# valve.net
KiCad netlist of a schematic drawn in EAGLE
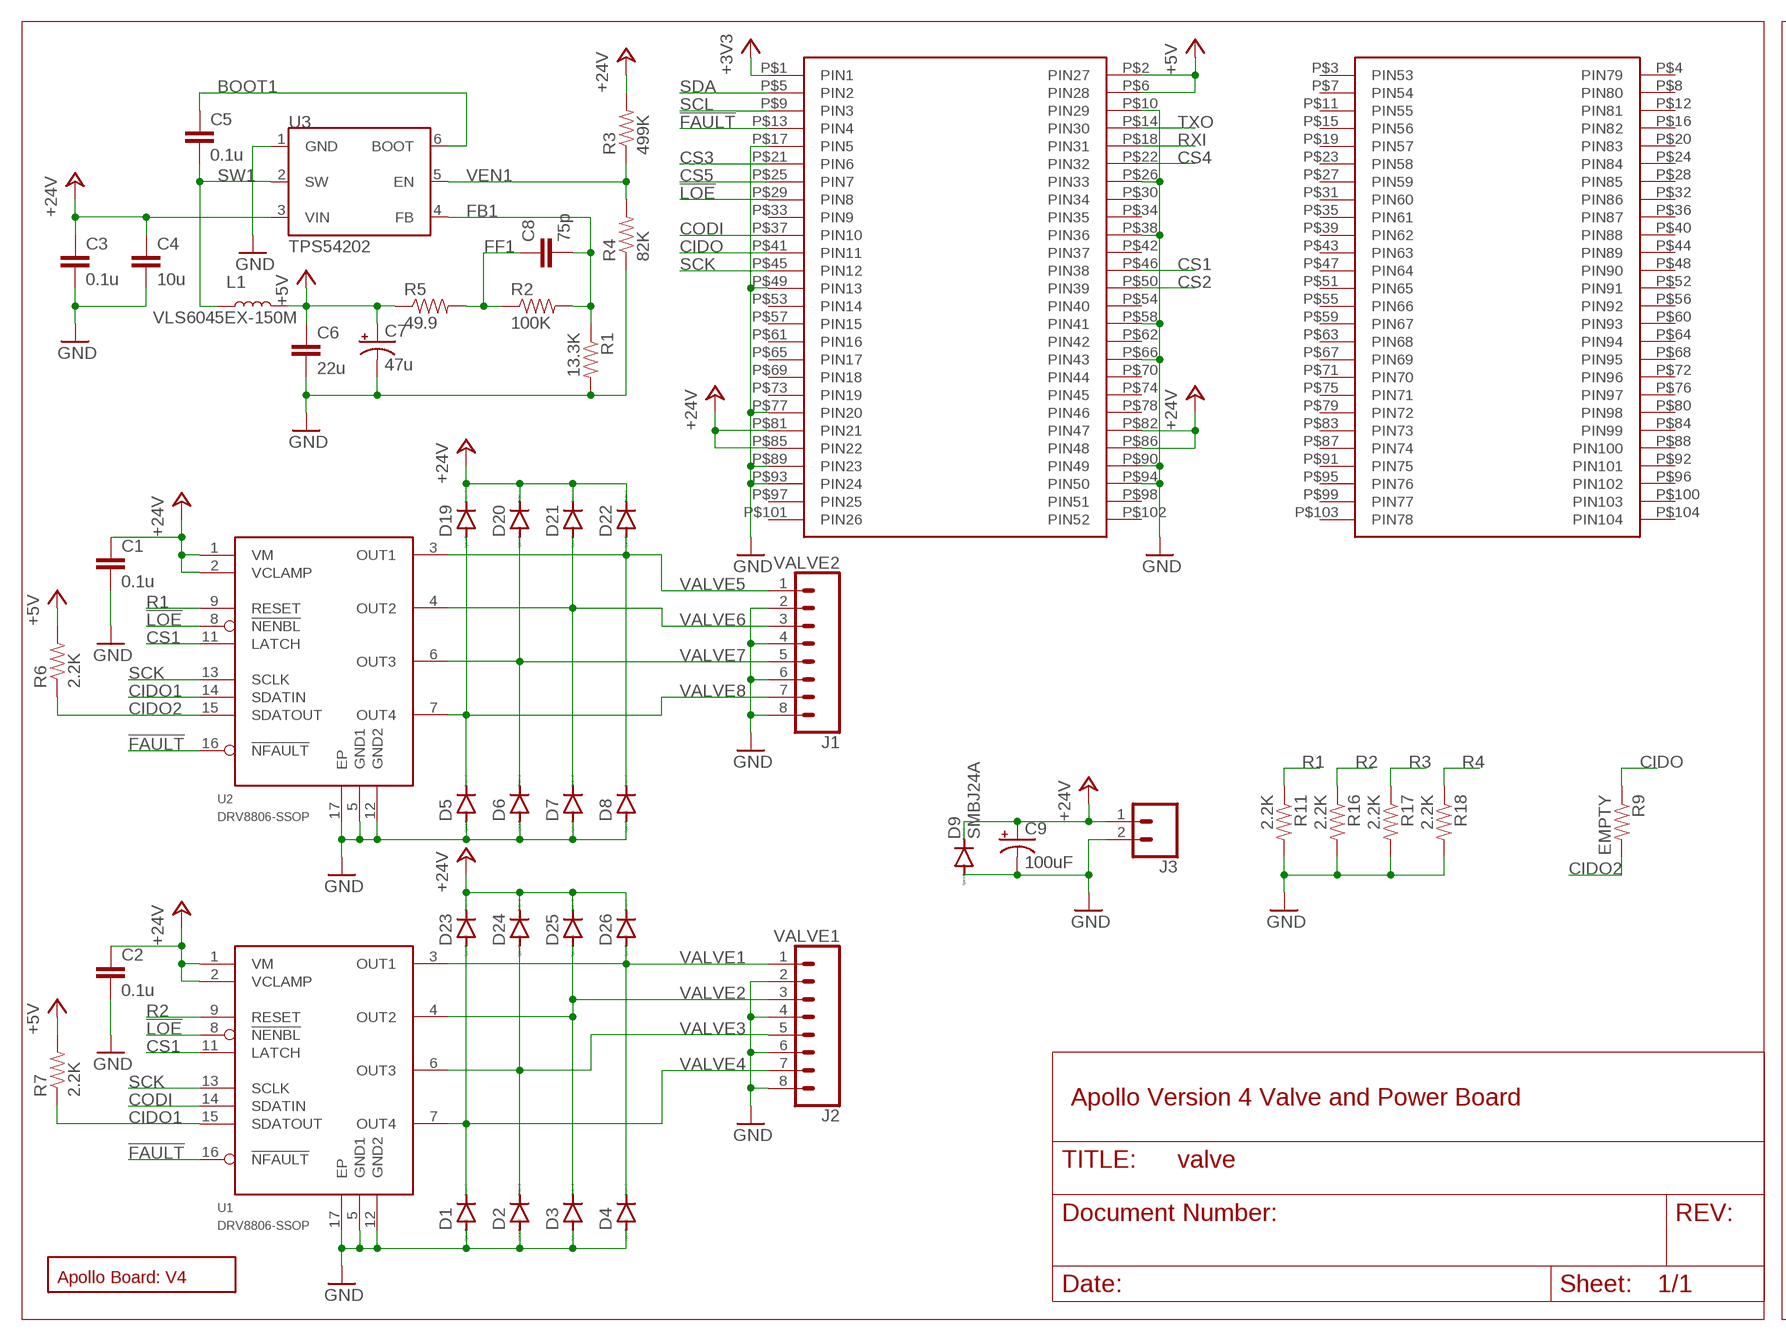
[diagram p0: schematic, sheet 1, part 1 of 2]
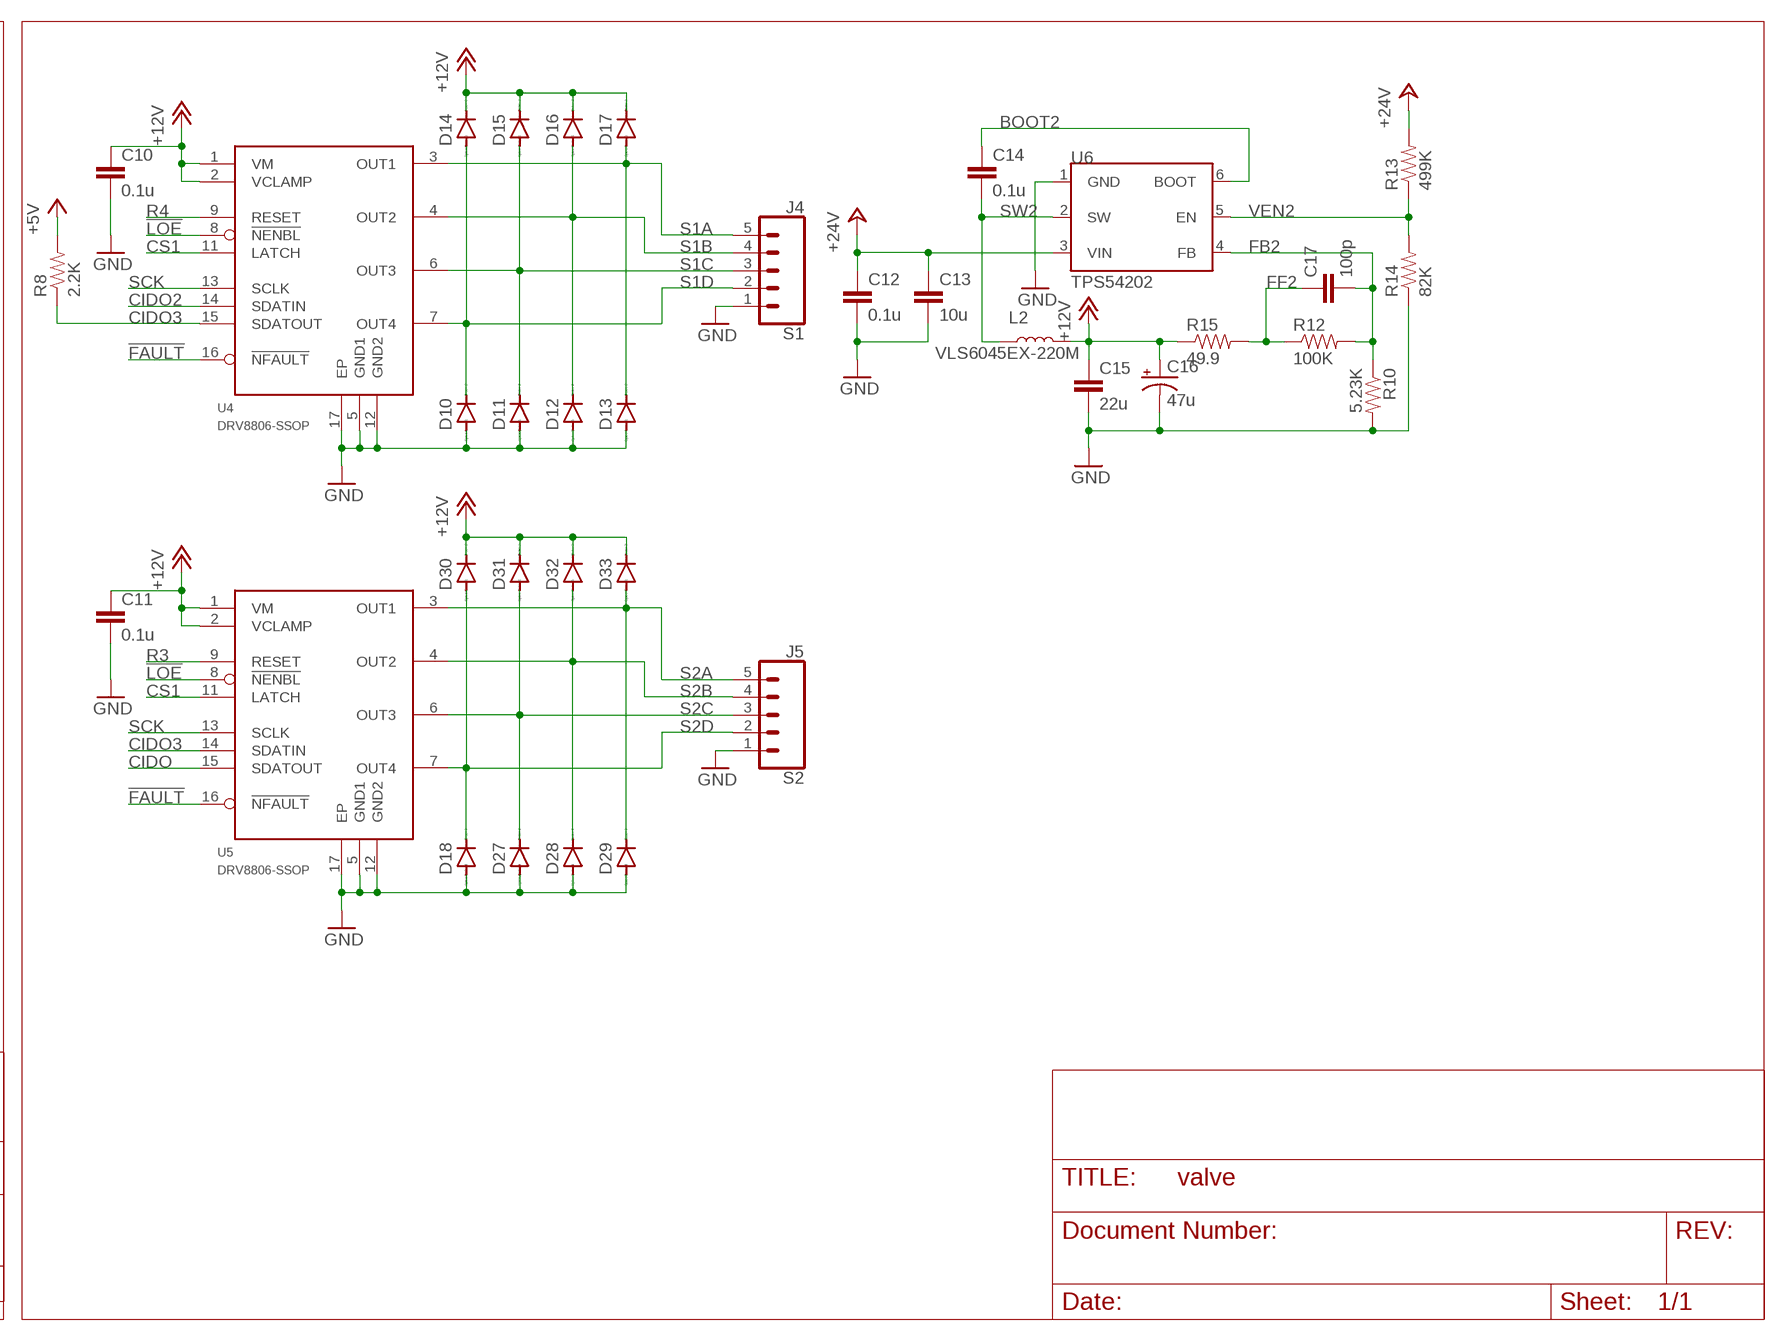
[diagram p1: schematic, sheet 1, part 2 of 2]

(export (version "E")
  (design (tool "Eeschema 10.0.6"))
  (components
    (comp (ref "C1")
      (value "0.1u")
      (footprint "eagle-import:0805")
      (libsource (lib "eagle-import") (part "CAP0805"))
    )
    (comp (ref "C2")
      (value "0.1u")
      (footprint "eagle-import:0805")
      (libsource (lib "eagle-import") (part "CAP0805"))
    )
    (comp (ref "C3")
      (value "0.1u")
      (footprint "eagle-import:0805")
      (libsource (lib "eagle-import") (part "CAP0805"))
    )
    (comp (ref "C4")
      (value "10u")
      (footprint "eagle-import:0805")
      (libsource (lib "eagle-import") (part "CAP0805"))
    )
    (comp (ref "C5")
      (value "0.1u")
      (footprint "eagle-import:0805")
      (libsource (lib "eagle-import") (part "CAP0805"))
    )
    (comp (ref "C6")
      (value "22u")
      (footprint "eagle-import:0805")
      (libsource (lib "eagle-import") (part "CAP0805"))
    )
    (comp (ref "C7")
      (value "47u")
      (footprint "eagle-import:PANASONIC_C")
      (libsource (lib "eagle-import") (part "CAP_POLC"))
    )
    (comp (ref "C8")
      (value "75p")
      (footprint "eagle-import:0805")
      (libsource (lib "eagle-import") (part "CAP0805"))
    )
    (comp (ref "C9")
      (value "100uF")
      (footprint "eagle-import:PANASONIC_D")
      (libsource (lib "eagle-import") (part "100UF-POLAR-25V-20%(ELEC)"))
    )
    (comp (ref "C10")
      (value "0.1u")
      (footprint "eagle-import:0805")
      (libsource (lib "eagle-import") (part "CAP0805"))
    )
    (comp (ref "C11")
      (value "0.1u")
      (footprint "eagle-import:0805")
      (libsource (lib "eagle-import") (part "CAP0805"))
    )
    (comp (ref "C12")
      (value "0.1u")
      (footprint "eagle-import:0805")
      (libsource (lib "eagle-import") (part "CAP0805"))
    )
    (comp (ref "C13")
      (value "10u")
      (footprint "eagle-import:0805")
      (libsource (lib "eagle-import") (part "CAP0805"))
    )
    (comp (ref "C14")
      (value "0.1u")
      (footprint "eagle-import:0805")
      (libsource (lib "eagle-import") (part "CAP0805"))
    )
    (comp (ref "C15")
      (value "22u")
      (footprint "eagle-import:0805")
      (libsource (lib "eagle-import") (part "CAP0805"))
    )
    (comp (ref "C16")
      (value "47u")
      (footprint "eagle-import:PANASONIC_C")
      (libsource (lib "eagle-import") (part "CAP_POLC"))
    )
    (comp (ref "C17")
      (value "100p")
      (footprint "eagle-import:0805")
      (libsource (lib "eagle-import") (part "CAP0805"))
    )
    (comp (ref "D1")
      (value "B5819W")
      (footprint "eagle-import:SOD123")
      (libsource (lib "eagle-import") (part "DIODE-SOD123"))
    )
    (comp (ref "D2")
      (value "B5819W")
      (footprint "eagle-import:SOD123")
      (libsource (lib "eagle-import") (part "DIODE-SOD123"))
    )
    (comp (ref "D3")
      (value "B5819W")
      (footprint "eagle-import:SOD123")
      (libsource (lib "eagle-import") (part "DIODE-SOD123"))
    )
    (comp (ref "D4")
      (value "B5819W")
      (footprint "eagle-import:SOD123")
      (libsource (lib "eagle-import") (part "DIODE-SOD123"))
    )
    (comp (ref "D5")
      (value "B5819W")
      (footprint "eagle-import:SOD123")
      (libsource (lib "eagle-import") (part "DIODE-SOD123"))
    )
    (comp (ref "D6")
      (value "B5819W")
      (footprint "eagle-import:SOD123")
      (libsource (lib "eagle-import") (part "DIODE-SOD123"))
    )
    (comp (ref "D7")
      (value "B5819W")
      (footprint "eagle-import:SOD123")
      (libsource (lib "eagle-import") (part "DIODE-SOD123"))
    )
    (comp (ref "D8")
      (value "B5819W")
      (footprint "eagle-import:SOD123")
      (libsource (lib "eagle-import") (part "DIODE-SOD123"))
    )
    (comp (ref "D9")
      (value "SMBJ24A")
      (footprint "eagle-import:SMB")
      (libsource (lib "eagle-import") (part "DIODE-SMB"))
    )
    (comp (ref "D10")
      (value "B5819W")
      (footprint "eagle-import:SOD123")
      (libsource (lib "eagle-import") (part "DIODE-SOD123"))
    )
    (comp (ref "D11")
      (value "B5819W")
      (footprint "eagle-import:SOD123")
      (libsource (lib "eagle-import") (part "DIODE-SOD123"))
    )
    (comp (ref "D12")
      (value "B5819W")
      (footprint "eagle-import:SOD123")
      (libsource (lib "eagle-import") (part "DIODE-SOD123"))
    )
    (comp (ref "D13")
      (value "B5819W")
      (footprint "eagle-import:SOD123")
      (libsource (lib "eagle-import") (part "DIODE-SOD123"))
    )
    (comp (ref "D14")
      (value "B5819W")
      (footprint "eagle-import:SOD123")
      (libsource (lib "eagle-import") (part "DIODE-SOD123"))
    )
    (comp (ref "D15")
      (value "B5819W")
      (footprint "eagle-import:SOD123")
      (libsource (lib "eagle-import") (part "DIODE-SOD123"))
    )
    (comp (ref "D16")
      (value "B5819W")
      (footprint "eagle-import:SOD123")
      (libsource (lib "eagle-import") (part "DIODE-SOD123"))
    )
    (comp (ref "D17")
      (value "B5819W")
      (footprint "eagle-import:SOD123")
      (libsource (lib "eagle-import") (part "DIODE-SOD123"))
    )
    (comp (ref "D18")
      (value "B5819W")
      (footprint "eagle-import:SOD123")
      (libsource (lib "eagle-import") (part "DIODE-SOD123"))
    )
    (comp (ref "D19")
      (value "B5819W")
      (footprint "eagle-import:SOD123")
      (libsource (lib "eagle-import") (part "DIODE-SOD123"))
    )
    (comp (ref "D20")
      (value "B5819W")
      (footprint "eagle-import:SOD123")
      (libsource (lib "eagle-import") (part "DIODE-SOD123"))
    )
    (comp (ref "D21")
      (value "B5819W")
      (footprint "eagle-import:SOD123")
      (libsource (lib "eagle-import") (part "DIODE-SOD123"))
    )
    (comp (ref "D22")
      (value "B5819W")
      (footprint "eagle-import:SOD123")
      (libsource (lib "eagle-import") (part "DIODE-SOD123"))
    )
    (comp (ref "D23")
      (value "B5819W")
      (footprint "eagle-import:SOD123")
      (libsource (lib "eagle-import") (part "DIODE-SOD123"))
    )
    (comp (ref "D24")
      (value "B5819W")
      (footprint "eagle-import:SOD123")
      (libsource (lib "eagle-import") (part "DIODE-SOD123"))
    )
    (comp (ref "D25")
      (value "B5819W")
      (footprint "eagle-import:SOD123")
      (libsource (lib "eagle-import") (part "DIODE-SOD123"))
    )
    (comp (ref "D26")
      (value "B5819W")
      (footprint "eagle-import:SOD123")
      (libsource (lib "eagle-import") (part "DIODE-SOD123"))
    )
    (comp (ref "D27")
      (value "B5819W")
      (footprint "eagle-import:SOD123")
      (libsource (lib "eagle-import") (part "DIODE-SOD123"))
    )
    (comp (ref "D28")
      (value "B5819W")
      (footprint "eagle-import:SOD123")
      (libsource (lib "eagle-import") (part "DIODE-SOD123"))
    )
    (comp (ref "D29")
      (value "B5819W")
      (footprint "eagle-import:SOD123")
      (libsource (lib "eagle-import") (part "DIODE-SOD123"))
    )
    (comp (ref "D30")
      (value "B5819W")
      (footprint "eagle-import:SOD123")
      (libsource (lib "eagle-import") (part "DIODE-SOD123"))
    )
    (comp (ref "D31")
      (value "B5819W")
      (footprint "eagle-import:SOD123")
      (libsource (lib "eagle-import") (part "DIODE-SOD123"))
    )
    (comp (ref "D32")
      (value "B5819W")
      (footprint "eagle-import:SOD123")
      (libsource (lib "eagle-import") (part "DIODE-SOD123"))
    )
    (comp (ref "D33")
      (value "B5819W")
      (footprint "eagle-import:SOD123")
      (libsource (lib "eagle-import") (part "DIODE-SOD123"))
    )
    (comp (ref "J1")
      (value "VALVE2")
      (footprint "eagle-import:SCREWTERMINAL-3.5MM-8")
      (libsource (lib "eagle-import") (part "CONN_083.5MM-8"))
    )
    (comp (ref "J2")
      (value "VALVE1")
      (footprint "eagle-import:SCREWTERMINAL-3.5MM-8")
      (libsource (lib "eagle-import") (part "CONN_083.5MM-8"))
    )
    (comp (ref "J3")
      (value "CONN_023.5MM")
      (footprint "eagle-import:SCREWTERMINAL-3.5MM-2")
      (libsource (lib "eagle-import") (part "CONN_023.5MM"))
    )
    (comp (ref "J4")
      (value "S1")
      (footprint "eagle-import:JST-5-PTH")
      (libsource (lib "eagle-import") (part "CONN_05JST"))
    )
    (comp (ref "J5")
      (value "S2")
      (footprint "eagle-import:JST-5-PTH")
      (libsource (lib "eagle-import") (part "CONN_05JST"))
    )
    (comp (ref "L1")
      (value "VLS6045EX-150M")
      (footprint "eagle-import:VLS6045EX")
      (libsource (lib "eagle-import") (part "VLS6045EX-H"))
    )
    (comp (ref "L2")
      (value "VLS6045EX-220M")
      (footprint "eagle-import:VLS6045EX")
      (libsource (lib "eagle-import") (part "VLS6045EX-H"))
    )
    (comp (ref "R1")
      (value "13.3K")
      (footprint "eagle-import:0805")
      (libsource (lib "eagle-import") (part "RESISTOR0805-RES"))
    )
    (comp (ref "R2")
      (value "100K")
      (footprint "eagle-import:0805")
      (libsource (lib "eagle-import") (part "RESISTOR0805-RES"))
    )
    (comp (ref "R3")
      (value "499K")
      (footprint "eagle-import:0805")
      (libsource (lib "eagle-import") (part "RESISTOR0805-RES"))
    )
    (comp (ref "R4")
      (value "82K")
      (footprint "eagle-import:0805")
      (libsource (lib "eagle-import") (part "RESISTOR0805-RES"))
    )
    (comp (ref "R5")
      (value "49.9")
      (footprint "eagle-import:0805")
      (libsource (lib "eagle-import") (part "RESISTOR0805-RES"))
    )
    (comp (ref "R6")
      (value "2.2K")
      (footprint "eagle-import:0805")
      (libsource (lib "eagle-import") (part "RESISTOR0805-RES"))
    )
    (comp (ref "R7")
      (value "2.2K")
      (footprint "eagle-import:0805")
      (libsource (lib "eagle-import") (part "RESISTOR0805-RES"))
    )
    (comp (ref "R8")
      (value "2.2K")
      (footprint "eagle-import:0805")
      (libsource (lib "eagle-import") (part "RESISTOR0805-RES"))
    )
    (comp (ref "R9")
      (value "EMPTY")
      (footprint "eagle-import:0805")
      (libsource (lib "eagle-import") (part "RESISTOR0805-RES"))
    )
    (comp (ref "R10")
      (value "5.23K")
      (footprint "eagle-import:0805")
      (libsource (lib "eagle-import") (part "RESISTOR0805-RES"))
    )
    (comp (ref "R11")
      (value "2.2K")
      (footprint "eagle-import:0805")
      (libsource (lib "eagle-import") (part "RESISTOR0805-RES"))
    )
    (comp (ref "R12")
      (value "100K")
      (footprint "eagle-import:0805")
      (libsource (lib "eagle-import") (part "RESISTOR0805-RES"))
    )
    (comp (ref "R13")
      (value "499K")
      (footprint "eagle-import:0805")
      (libsource (lib "eagle-import") (part "RESISTOR0805-RES"))
    )
    (comp (ref "R14")
      (value "82K")
      (footprint "eagle-import:0805")
      (libsource (lib "eagle-import") (part "RESISTOR0805-RES"))
    )
    (comp (ref "R15")
      (value "49.9")
      (footprint "eagle-import:0805")
      (libsource (lib "eagle-import") (part "RESISTOR0805-RES"))
    )
    (comp (ref "R16")
      (value "2.2K")
      (footprint "eagle-import:0805")
      (libsource (lib "eagle-import") (part "RESISTOR0805-RES"))
    )
    (comp (ref "R17")
      (value "2.2K")
      (footprint "eagle-import:0805")
      (libsource (lib "eagle-import") (part "RESISTOR0805-RES"))
    )
    (comp (ref "R18")
      (value "2.2K")
      (footprint "eagle-import:0805")
      (libsource (lib "eagle-import") (part "RESISTOR0805-RES"))
    )
    (comp (ref "U$1")
      (value "PC104_CONNECTOR")
      (footprint "eagle-import:PC104_CONNECTOR")
      (libsource (lib "eagle-import") (part "PC104_CONNECTOR"))
    )
    (comp (ref "U$2")
      (value "BOARD_TEMPLATE1")
      (footprint "eagle-import:BOARD_TEMPLATE")
      (libsource (lib "eagle-import") (part "BOARD_TEMPLATE1"))
    )
    (comp (ref "U1")
      (value "DRV8806-SSOP")
      (footprint "eagle-import:SOP65P640X120-17N")
      (libsource (lib "eagle-import") (part "DRV8806-SSOP"))
    )
    (comp (ref "U2")
      (value "DRV8806-SSOP")
      (footprint "eagle-import:SOP65P640X120-17N")
      (libsource (lib "eagle-import") (part "DRV8806-SSOP"))
    )
    (comp (ref "U3")
      (value "TPS54202")
      (footprint "eagle-import:SOT23-6L")
      (libsource (lib "eagle-import") (part "TPS54202"))
    )
    (comp (ref "U4")
      (value "DRV8806-SSOP")
      (footprint "eagle-import:SOP65P640X120-17N")
      (libsource (lib "eagle-import") (part "DRV8806-SSOP"))
    )
    (comp (ref "U5")
      (value "DRV8806-SSOP")
      (footprint "eagle-import:SOP65P640X120-17N")
      (libsource (lib "eagle-import") (part "DRV8806-SSOP"))
    )
    (comp (ref "U6")
      (value "TPS54202")
      (footprint "eagle-import:SOT23-6L")
      (libsource (lib "eagle-import") (part "TPS54202"))
    )
  )
  (nets
    (net (code "1") (name "+3V3") (class "Default")
      (node (ref "U$1") (pin "P$1") (pinfunction "PIN1_P$1") (pintype "bidirectional"))
    )
    (net (code "2") (name "+5V") (class "Default")
      (node (ref "C6") (pin "1") (pinfunction "1_1") (pintype "passive"))
      (node (ref "C7") (pin "+") (pinfunction "+_+") (pintype "passive"))
      (node (ref "L1") (pin "2") (pinfunction "2_2") (pintype "passive"))
      (node (ref "R5") (pin "1") (pinfunction "1_1") (pintype "passive"))
      (node (ref "R6") (pin "2") (pinfunction "2_2") (pintype "passive"))
      (node (ref "R7") (pin "2") (pinfunction "2_2") (pintype "passive"))
      (node (ref "R8") (pin "2") (pinfunction "2_2") (pintype "passive"))
      (node (ref "U$1") (pin "P$2") (pinfunction "PIN27_P$2") (pintype "bidirectional"))
      (node (ref "U$1") (pin "P$6") (pinfunction "PIN28_P$6") (pintype "bidirectional"))
    )
    (net (code "3") (name "+12V") (class "Default")
      (node (ref "C10") (pin "1") (pinfunction "1_1") (pintype "passive"))
      (node (ref "C11") (pin "1") (pinfunction "1_1") (pintype "passive"))
      (node (ref "C15") (pin "1") (pinfunction "1_1") (pintype "passive"))
      (node (ref "C16") (pin "+") (pinfunction "+_+") (pintype "passive"))
      (node (ref "D14") (pin "C") (pinfunction "C_C") (pintype "passive"))
      (node (ref "D15") (pin "C") (pinfunction "C_C") (pintype "passive"))
      (node (ref "D16") (pin "C") (pinfunction "C_C") (pintype "passive"))
      (node (ref "D17") (pin "C") (pinfunction "C_C") (pintype "passive"))
      (node (ref "D30") (pin "C") (pinfunction "C_C") (pintype "passive"))
      (node (ref "D31") (pin "C") (pinfunction "C_C") (pintype "passive"))
      (node (ref "D32") (pin "C") (pinfunction "C_C") (pintype "passive"))
      (node (ref "D33") (pin "C") (pinfunction "C_C") (pintype "passive"))
      (node (ref "L2") (pin "2") (pinfunction "2_2") (pintype "passive"))
      (node (ref "R15") (pin "1") (pinfunction "1_1") (pintype "passive"))
      (node (ref "U4") (pin "1") (pinfunction "VM_1") (pintype "input"))
      (node (ref "U4") (pin "2") (pinfunction "VCLAMP_2") (pintype "input"))
      (node (ref "U5") (pin "1") (pinfunction "VM_1") (pintype "input"))
      (node (ref "U5") (pin "2") (pinfunction "VCLAMP_2") (pintype "input"))
    )
    (net (code "4") (name "+24V") (class "Default")
      (node (ref "C1") (pin "1") (pinfunction "1_1") (pintype "passive"))
      (node (ref "C12") (pin "1") (pinfunction "1_1") (pintype "passive"))
      (node (ref "C13") (pin "1") (pinfunction "1_1") (pintype "passive"))
      (node (ref "C2") (pin "1") (pinfunction "1_1") (pintype "passive"))
      (node (ref "C3") (pin "1") (pinfunction "1_1") (pintype "passive"))
      (node (ref "C4") (pin "1") (pinfunction "1_1") (pintype "passive"))
      (node (ref "C9") (pin "+") (pinfunction "+_+") (pintype "passive"))
      (node (ref "D19") (pin "C") (pinfunction "C_C") (pintype "passive"))
      (node (ref "D20") (pin "C") (pinfunction "C_C") (pintype "passive"))
      (node (ref "D21") (pin "C") (pinfunction "C_C") (pintype "passive"))
      (node (ref "D22") (pin "C") (pinfunction "C_C") (pintype "passive"))
      (node (ref "D23") (pin "C") (pinfunction "C_C") (pintype "passive"))
      (node (ref "D24") (pin "C") (pinfunction "C_C") (pintype "passive"))
      (node (ref "D25") (pin "C") (pinfunction "C_C") (pintype "passive"))
      (node (ref "D26") (pin "C") (pinfunction "C_C") (pintype "passive"))
      (node (ref "D9") (pin "C") (pinfunction "C_C") (pintype "passive"))
      (node (ref "J3") (pin "1") (pinfunction "1_1") (pintype "passive"))
      (node (ref "R13") (pin "2") (pinfunction "2_2") (pintype "passive"))
      (node (ref "R3") (pin "2") (pinfunction "2_2") (pintype "passive"))
      (node (ref "U$1") (pin "P$81") (pinfunction "PIN21_P$81") (pintype "bidirectional"))
      (node (ref "U$1") (pin "P$82") (pinfunction "PIN47_P$82") (pintype "bidirectional"))
      (node (ref "U$1") (pin "P$85") (pinfunction "PIN22_P$85") (pintype "bidirectional"))
      (node (ref "U$1") (pin "P$86") (pinfunction "PIN48_P$86") (pintype "bidirectional"))
      (node (ref "U1") (pin "1") (pinfunction "VM_1") (pintype "input"))
      (node (ref "U1") (pin "2") (pinfunction "VCLAMP_2") (pintype "input"))
      (node (ref "U2") (pin "1") (pinfunction "VM_1") (pintype "input"))
      (node (ref "U2") (pin "2") (pinfunction "VCLAMP_2") (pintype "input"))
      (node (ref "U3") (pin "3") (pinfunction "VIN_3") (pintype "power_in"))
      (node (ref "U6") (pin "3") (pinfunction "VIN_3") (pintype "power_in"))
    )
    (net (code "5") (name "/BOOT1") (class "Default")
      (node (ref "C5") (pin "1") (pinfunction "1_1") (pintype "passive"))
      (node (ref "U3") (pin "6") (pinfunction "BOOT_6") (pintype "passive"))
    )
    (net (code "6") (name "/BOOT2") (class "Default")
      (node (ref "C14") (pin "1") (pinfunction "1_1") (pintype "passive"))
      (node (ref "U6") (pin "6") (pinfunction "BOOT_6") (pintype "passive"))
    )
    (net (code "7") (name "/CIDO") (class "Default")
      (node (ref "R9") (pin "1") (pinfunction "1_1") (pintype "passive"))
      (node (ref "U$1") (pin "P$41") (pinfunction "PIN11_P$41") (pintype "bidirectional"))
      (node (ref "U5") (pin "15") (pinfunction "SDATOUT_15") (pintype "output"))
    )
    (net (code "8") (name "/CIDO1") (class "Default")
      (node (ref "R7") (pin "1") (pinfunction "1_1") (pintype "passive"))
      (node (ref "U1") (pin "15") (pinfunction "SDATOUT_15") (pintype "output"))
      (node (ref "U2") (pin "14") (pinfunction "SDATIN_14") (pintype "input"))
    )
    (net (code "9") (name "/CIDO2") (class "Default")
      (node (ref "R6") (pin "1") (pinfunction "1_1") (pintype "passive"))
      (node (ref "R9") (pin "2") (pinfunction "2_2") (pintype "passive"))
      (node (ref "U2") (pin "15") (pinfunction "SDATOUT_15") (pintype "output"))
      (node (ref "U4") (pin "14") (pinfunction "SDATIN_14") (pintype "input"))
    )
    (net (code "10") (name "/CIDO3") (class "Default")
      (node (ref "R8") (pin "1") (pinfunction "1_1") (pintype "passive"))
      (node (ref "U4") (pin "15") (pinfunction "SDATOUT_15") (pintype "output"))
      (node (ref "U5") (pin "14") (pinfunction "SDATIN_14") (pintype "input"))
    )
    (net (code "11") (name "/CODI") (class "Default")
      (node (ref "U$1") (pin "P$37") (pinfunction "PIN10_P$37") (pintype "bidirectional"))
      (node (ref "U1") (pin "14") (pinfunction "SDATIN_14") (pintype "input"))
    )
    (net (code "12") (name "/CS1") (class "Default")
      (node (ref "U$1") (pin "P$46") (pinfunction "PIN38_P$46") (pintype "bidirectional"))
      (node (ref "U1") (pin "11") (pinfunction "LATCH_11") (pintype "input"))
      (node (ref "U2") (pin "11") (pinfunction "LATCH_11") (pintype "input"))
      (node (ref "U4") (pin "11") (pinfunction "LATCH_11") (pintype "input"))
      (node (ref "U5") (pin "11") (pinfunction "LATCH_11") (pintype "input"))
    )
    (net (code "13") (name "/CS2") (class "Default")
      (node (ref "U$1") (pin "P$50") (pinfunction "PIN39_P$50") (pintype "bidirectional"))
    )
    (net (code "14") (name "/CS3") (class "Default")
      (node (ref "U$1") (pin "P$21") (pinfunction "PIN6_P$21") (pintype "bidirectional"))
    )
    (net (code "15") (name "/CS4") (class "Default")
      (node (ref "U$1") (pin "P$22") (pinfunction "PIN32_P$22") (pintype "bidirectional"))
    )
    (net (code "16") (name "/CS5") (class "Default")
      (node (ref "U$1") (pin "P$25") (pinfunction "PIN7_P$25") (pintype "bidirectional"))
    )
    (net (code "17") (name "/FB1") (class "Default")
      (node (ref "C8") (pin "2") (pinfunction "2_2") (pintype "passive"))
      (node (ref "R1") (pin "1") (pinfunction "1_1") (pintype "passive"))
      (node (ref "R2") (pin "2") (pinfunction "2_2") (pintype "passive"))
      (node (ref "U3") (pin "4") (pinfunction "FB_4") (pintype "passive"))
    )
    (net (code "18") (name "/FB2") (class "Default")
      (node (ref "C17") (pin "2") (pinfunction "2_2") (pintype "passive"))
      (node (ref "R10") (pin "1") (pinfunction "1_1") (pintype "passive"))
      (node (ref "R12") (pin "2") (pinfunction "2_2") (pintype "passive"))
      (node (ref "U6") (pin "4") (pinfunction "FB_4") (pintype "passive"))
    )
    (net (code "19") (name "/FF1") (class "Default")
      (node (ref "C8") (pin "1") (pinfunction "1_1") (pintype "passive"))
      (node (ref "R2") (pin "1") (pinfunction "1_1") (pintype "passive"))
      (node (ref "R5") (pin "2") (pinfunction "2_2") (pintype "passive"))
    )
    (net (code "20") (name "/FF2") (class "Default")
      (node (ref "C17") (pin "1") (pinfunction "1_1") (pintype "passive"))
      (node (ref "R12") (pin "1") (pinfunction "1_1") (pintype "passive"))
      (node (ref "R15") (pin "2") (pinfunction "2_2") (pintype "passive"))
    )
    (net (code "21") (name "/R1") (class "Default")
      (node (ref "R11") (pin "1") (pinfunction "1_1") (pintype "passive"))
      (node (ref "U2") (pin "9") (pinfunction "RESET_9") (pintype "input"))
    )
    (net (code "22") (name "/R2") (class "Default")
      (node (ref "R16") (pin "1") (pinfunction "1_1") (pintype "passive"))
      (node (ref "U1") (pin "9") (pinfunction "RESET_9") (pintype "input"))
    )
    (net (code "23") (name "/R3") (class "Default")
      (node (ref "R17") (pin "1") (pinfunction "1_1") (pintype "passive"))
      (node (ref "U5") (pin "9") (pinfunction "RESET_9") (pintype "input"))
    )
    (net (code "24") (name "/R4") (class "Default")
      (node (ref "R18") (pin "1") (pinfunction "1_1") (pintype "passive"))
      (node (ref "U4") (pin "9") (pinfunction "RESET_9") (pintype "input"))
    )
    (net (code "25") (name "/RXI") (class "Default")
      (node (ref "U$1") (pin "P$18") (pinfunction "PIN31_P$18") (pintype "bidirectional"))
    )
    (net (code "26") (name "/S1A") (class "Default")
      (node (ref "D13") (pin "C") (pinfunction "C_C") (pintype "passive"))
      (node (ref "D17") (pin "A") (pinfunction "A_A") (pintype "passive"))
      (node (ref "J4") (pin "5") (pinfunction "5_5") (pintype "passive"))
      (node (ref "U4") (pin "3") (pinfunction "OUT1_3") (pintype "output"))
    )
    (net (code "27") (name "/S1B") (class "Default")
      (node (ref "D12") (pin "C") (pinfunction "C_C") (pintype "passive"))
      (node (ref "D16") (pin "A") (pinfunction "A_A") (pintype "passive"))
      (node (ref "J4") (pin "4") (pinfunction "4_4") (pintype "passive"))
      (node (ref "U4") (pin "4") (pinfunction "OUT2_4") (pintype "output"))
    )
    (net (code "28") (name "/S1C") (class "Default")
      (node (ref "D11") (pin "C") (pinfunction "C_C") (pintype "passive"))
      (node (ref "D15") (pin "A") (pinfunction "A_A") (pintype "passive"))
      (node (ref "J4") (pin "3") (pinfunction "3_3") (pintype "passive"))
      (node (ref "U4") (pin "6") (pinfunction "OUT3_6") (pintype "output"))
    )
    (net (code "29") (name "/S1D") (class "Default")
      (node (ref "D10") (pin "C") (pinfunction "C_C") (pintype "passive"))
      (node (ref "D14") (pin "A") (pinfunction "A_A") (pintype "passive"))
      (node (ref "J4") (pin "2") (pinfunction "2_2") (pintype "passive"))
      (node (ref "U4") (pin "7") (pinfunction "OUT4_7") (pintype "output"))
    )
    (net (code "30") (name "/S2A") (class "Default")
      (node (ref "D29") (pin "C") (pinfunction "C_C") (pintype "passive"))
      (node (ref "D33") (pin "A") (pinfunction "A_A") (pintype "passive"))
      (node (ref "J5") (pin "5") (pinfunction "5_5") (pintype "passive"))
      (node (ref "U5") (pin "3") (pinfunction "OUT1_3") (pintype "output"))
    )
    (net (code "31") (name "/S2B") (class "Default")
      (node (ref "D28") (pin "C") (pinfunction "C_C") (pintype "passive"))
      (node (ref "D32") (pin "A") (pinfunction "A_A") (pintype "passive"))
      (node (ref "J5") (pin "4") (pinfunction "4_4") (pintype "passive"))
      (node (ref "U5") (pin "4") (pinfunction "OUT2_4") (pintype "output"))
    )
    (net (code "32") (name "/S2C") (class "Default")
      (node (ref "D27") (pin "C") (pinfunction "C_C") (pintype "passive"))
      (node (ref "D31") (pin "A") (pinfunction "A_A") (pintype "passive"))
      (node (ref "J5") (pin "3") (pinfunction "3_3") (pintype "passive"))
      (node (ref "U5") (pin "6") (pinfunction "OUT3_6") (pintype "output"))
    )
    (net (code "33") (name "/S2D") (class "Default")
      (node (ref "D18") (pin "C") (pinfunction "C_C") (pintype "passive"))
      (node (ref "D30") (pin "A") (pinfunction "A_A") (pintype "passive"))
      (node (ref "J5") (pin "2") (pinfunction "2_2") (pintype "passive"))
      (node (ref "U5") (pin "7") (pinfunction "OUT4_7") (pintype "output"))
    )
    (net (code "34") (name "/SCK") (class "Default")
      (node (ref "U$1") (pin "P$45") (pinfunction "PIN12_P$45") (pintype "bidirectional"))
      (node (ref "U1") (pin "13") (pinfunction "SCLK_13") (pintype "input"))
      (node (ref "U2") (pin "13") (pinfunction "SCLK_13") (pintype "input"))
      (node (ref "U4") (pin "13") (pinfunction "SCLK_13") (pintype "input"))
      (node (ref "U5") (pin "13") (pinfunction "SCLK_13") (pintype "input"))
    )
    (net (code "35") (name "/SCL") (class "Default")
      (node (ref "U$1") (pin "P$9") (pinfunction "PIN3_P$9") (pintype "bidirectional"))
    )
    (net (code "36") (name "/SDA") (class "Default")
      (node (ref "U$1") (pin "P$5") (pinfunction "PIN2_P$5") (pintype "bidirectional"))
    )
    (net (code "37") (name "/SW1") (class "Default")
      (node (ref "C5") (pin "2") (pinfunction "2_2") (pintype "passive"))
      (node (ref "L1") (pin "1") (pinfunction "1_1") (pintype "passive"))
      (node (ref "U3") (pin "2") (pinfunction "SW_2") (pintype "output"))
    )
    (net (code "38") (name "/SW2") (class "Default")
      (node (ref "C14") (pin "2") (pinfunction "2_2") (pintype "passive"))
      (node (ref "L2") (pin "1") (pinfunction "1_1") (pintype "passive"))
      (node (ref "U6") (pin "2") (pinfunction "SW_2") (pintype "output"))
    )
    (net (code "39") (name "/TXO") (class "Default")
      (node (ref "U$1") (pin "P$14") (pinfunction "PIN30_P$14") (pintype "bidirectional"))
    )
    (net (code "40") (name "/VALVE1") (class "Default")
      (node (ref "D26") (pin "A") (pinfunction "A_A") (pintype "passive"))
      (node (ref "D4") (pin "C") (pinfunction "C_C") (pintype "passive"))
      (node (ref "J2") (pin "1") (pinfunction "1_1") (pintype "passive"))
      (node (ref "U1") (pin "3") (pinfunction "OUT1_3") (pintype "output"))
    )
    (net (code "41") (name "/VALVE2") (class "Default")
      (node (ref "D25") (pin "A") (pinfunction "A_A") (pintype "passive"))
      (node (ref "D3") (pin "C") (pinfunction "C_C") (pintype "passive"))
      (node (ref "J2") (pin "3") (pinfunction "3_3") (pintype "passive"))
      (node (ref "U1") (pin "4") (pinfunction "OUT2_4") (pintype "output"))
    )
    (net (code "42") (name "/VALVE3") (class "Default")
      (node (ref "D2") (pin "C") (pinfunction "C_C") (pintype "passive"))
      (node (ref "D24") (pin "A") (pinfunction "A_A") (pintype "passive"))
      (node (ref "J2") (pin "5") (pinfunction "5_5") (pintype "passive"))
      (node (ref "U1") (pin "6") (pinfunction "OUT3_6") (pintype "output"))
    )
    (net (code "43") (name "/VALVE4") (class "Default")
      (node (ref "D1") (pin "C") (pinfunction "C_C") (pintype "passive"))
      (node (ref "D23") (pin "A") (pinfunction "A_A") (pintype "passive"))
      (node (ref "J2") (pin "7") (pinfunction "7_7") (pintype "passive"))
      (node (ref "U1") (pin "7") (pinfunction "OUT4_7") (pintype "output"))
    )
    (net (code "44") (name "/VALVE5") (class "Default")
      (node (ref "D22") (pin "A") (pinfunction "A_A") (pintype "passive"))
      (node (ref "D8") (pin "C") (pinfunction "C_C") (pintype "passive"))
      (node (ref "J1") (pin "1") (pinfunction "1_1") (pintype "passive"))
      (node (ref "U2") (pin "3") (pinfunction "OUT1_3") (pintype "output"))
    )
    (net (code "45") (name "/VALVE6") (class "Default")
      (node (ref "D21") (pin "A") (pinfunction "A_A") (pintype "passive"))
      (node (ref "D7") (pin "C") (pinfunction "C_C") (pintype "passive"))
      (node (ref "J1") (pin "3") (pinfunction "3_3") (pintype "passive"))
      (node (ref "U2") (pin "4") (pinfunction "OUT2_4") (pintype "output"))
    )
    (net (code "46") (name "/VALVE7") (class "Default")
      (node (ref "D20") (pin "A") (pinfunction "A_A") (pintype "passive"))
      (node (ref "D6") (pin "C") (pinfunction "C_C") (pintype "passive"))
      (node (ref "J1") (pin "5") (pinfunction "5_5") (pintype "passive"))
      (node (ref "U2") (pin "6") (pinfunction "OUT3_6") (pintype "output"))
    )
    (net (code "47") (name "/VALVE8") (class "Default")
      (node (ref "D19") (pin "A") (pinfunction "A_A") (pintype "passive"))
      (node (ref "D5") (pin "C") (pinfunction "C_C") (pintype "passive"))
      (node (ref "J1") (pin "7") (pinfunction "7_7") (pintype "passive"))
      (node (ref "U2") (pin "7") (pinfunction "OUT4_7") (pintype "output"))
    )
    (net (code "48") (name "/VEN1") (class "Default")
      (node (ref "R3") (pin "1") (pinfunction "1_1") (pintype "passive"))
      (node (ref "R4") (pin "2") (pinfunction "2_2") (pintype "passive"))
      (node (ref "U3") (pin "5") (pinfunction "EN_5") (pintype "input"))
    )
    (net (code "49") (name "/VEN2") (class "Default")
      (node (ref "R13") (pin "1") (pinfunction "1_1") (pintype "passive"))
      (node (ref "R14") (pin "2") (pinfunction "2_2") (pintype "passive"))
      (node (ref "U6") (pin "5") (pinfunction "EN_5") (pintype "input"))
    )
    (net (code "50") (name "/~{FAULT}") (class "Default")
      (node (ref "U$1") (pin "P$13") (pinfunction "PIN4_P$13") (pintype "bidirectional"))
      (node (ref "U1") (pin "16") (pinfunction "~{NFAULT}_16") (pintype "output"))
      (node (ref "U2") (pin "16") (pinfunction "~{NFAULT}_16") (pintype "output"))
      (node (ref "U4") (pin "16") (pinfunction "~{NFAULT}_16") (pintype "output"))
      (node (ref "U5") (pin "16") (pinfunction "~{NFAULT}_16") (pintype "output"))
    )
    (net (code "51") (name "/~{LOE}") (class "Default")
      (node (ref "U$1") (pin "P$29") (pinfunction "PIN8_P$29") (pintype "bidirectional"))
      (node (ref "U1") (pin "8") (pinfunction "~{NENBL}_8") (pintype "input"))
      (node (ref "U2") (pin "8") (pinfunction "~{NENBL}_8") (pintype "input"))
      (node (ref "U4") (pin "8") (pinfunction "~{NENBL}_8") (pintype "input"))
      (node (ref "U5") (pin "8") (pinfunction "~{NENBL}_8") (pintype "input"))
    )
    (net (code "52") (name "GND") (class "Default")
      (node (ref "C1") (pin "2") (pinfunction "2_2") (pintype "passive"))
      (node (ref "C10") (pin "2") (pinfunction "2_2") (pintype "passive"))
      (node (ref "C11") (pin "2") (pinfunction "2_2") (pintype "passive"))
      (node (ref "C12") (pin "2") (pinfunction "2_2") (pintype "passive"))
      (node (ref "C13") (pin "2") (pinfunction "2_2") (pintype "passive"))
      (node (ref "C15") (pin "2") (pinfunction "2_2") (pintype "passive"))
      (node (ref "C16") (pin "-") (pinfunction "-_-") (pintype "passive"))
      (node (ref "C2") (pin "2") (pinfunction "2_2") (pintype "passive"))
      (node (ref "C3") (pin "2") (pinfunction "2_2") (pintype "passive"))
      (node (ref "C4") (pin "2") (pinfunction "2_2") (pintype "passive"))
      (node (ref "C6") (pin "2") (pinfunction "2_2") (pintype "passive"))
      (node (ref "C7") (pin "-") (pinfunction "-_-") (pintype "passive"))
      (node (ref "C9") (pin "-") (pinfunction "-_-") (pintype "passive"))
      (node (ref "D1") (pin "A") (pinfunction "A_A") (pintype "passive"))
      (node (ref "D10") (pin "A") (pinfunction "A_A") (pintype "passive"))
      (node (ref "D11") (pin "A") (pinfunction "A_A") (pintype "passive"))
      (node (ref "D12") (pin "A") (pinfunction "A_A") (pintype "passive"))
      (node (ref "D13") (pin "A") (pinfunction "A_A") (pintype "passive"))
      (node (ref "D18") (pin "A") (pinfunction "A_A") (pintype "passive"))
      (node (ref "D2") (pin "A") (pinfunction "A_A") (pintype "passive"))
      (node (ref "D27") (pin "A") (pinfunction "A_A") (pintype "passive"))
      (node (ref "D28") (pin "A") (pinfunction "A_A") (pintype "passive"))
      (node (ref "D29") (pin "A") (pinfunction "A_A") (pintype "passive"))
      (node (ref "D3") (pin "A") (pinfunction "A_A") (pintype "passive"))
      (node (ref "D4") (pin "A") (pinfunction "A_A") (pintype "passive"))
      (node (ref "D5") (pin "A") (pinfunction "A_A") (pintype "passive"))
      (node (ref "D6") (pin "A") (pinfunction "A_A") (pintype "passive"))
      (node (ref "D7") (pin "A") (pinfunction "A_A") (pintype "passive"))
      (node (ref "D8") (pin "A") (pinfunction "A_A") (pintype "passive"))
      (node (ref "D9") (pin "A") (pinfunction "A_A") (pintype "passive"))
      (node (ref "J1") (pin "2") (pinfunction "2_2") (pintype "passive"))
      (node (ref "J1") (pin "4") (pinfunction "4_4") (pintype "passive"))
      (node (ref "J1") (pin "6") (pinfunction "6_6") (pintype "passive"))
      (node (ref "J1") (pin "8") (pinfunction "8_8") (pintype "passive"))
      (node (ref "J2") (pin "2") (pinfunction "2_2") (pintype "passive"))
      (node (ref "J2") (pin "4") (pinfunction "4_4") (pintype "passive"))
      (node (ref "J2") (pin "6") (pinfunction "6_6") (pintype "passive"))
      (node (ref "J2") (pin "8") (pinfunction "8_8") (pintype "passive"))
      (node (ref "J3") (pin "2") (pinfunction "2_2") (pintype "passive"))
      (node (ref "J4") (pin "1") (pinfunction "1_1") (pintype "passive"))
      (node (ref "J5") (pin "1") (pinfunction "1_1") (pintype "passive"))
      (node (ref "R1") (pin "2") (pinfunction "2_2") (pintype "passive"))
      (node (ref "R10") (pin "2") (pinfunction "2_2") (pintype "passive"))
      (node (ref "R11") (pin "2") (pinfunction "2_2") (pintype "passive"))
      (node (ref "R14") (pin "1") (pinfunction "1_1") (pintype "passive"))
      (node (ref "R16") (pin "2") (pinfunction "2_2") (pintype "passive"))
      (node (ref "R17") (pin "2") (pinfunction "2_2") (pintype "passive"))
      (node (ref "R18") (pin "2") (pinfunction "2_2") (pintype "passive"))
      (node (ref "R4") (pin "1") (pinfunction "1_1") (pintype "passive"))
      (node (ref "U$1") (pin "P$10") (pinfunction "PIN29_P$10") (pintype "bidirectional"))
      (node (ref "U$1") (pin "P$17") (pinfunction "PIN5_P$17") (pintype "bidirectional"))
      (node (ref "U$1") (pin "P$26") (pinfunction "PIN33_P$26") (pintype "bidirectional"))
      (node (ref "U$1") (pin "P$38") (pinfunction "PIN36_P$38") (pintype "bidirectional"))
      (node (ref "U$1") (pin "P$49") (pinfunction "PIN13_P$49") (pintype "bidirectional"))
      (node (ref "U$1") (pin "P$58") (pinfunction "PIN41_P$58") (pintype "bidirectional"))
      (node (ref "U$1") (pin "P$66") (pinfunction "PIN43_P$66") (pintype "bidirectional"))
      (node (ref "U$1") (pin "P$77") (pinfunction "PIN20_P$77") (pintype "bidirectional"))
      (node (ref "U$1") (pin "P$89") (pinfunction "PIN23_P$89") (pintype "bidirectional"))
      (node (ref "U$1") (pin "P$90") (pinfunction "PIN49_P$90") (pintype "bidirectional"))
      (node (ref "U$1") (pin "P$93") (pinfunction "PIN24_P$93") (pintype "bidirectional"))
      (node (ref "U$1") (pin "P$94") (pinfunction "PIN50_P$94") (pintype "bidirectional"))
      (node (ref "U1") (pin "12") (pinfunction "GND2_12") (pintype "input"))
      (node (ref "U1") (pin "17") (pinfunction "EP_17") (pintype "input"))
      (node (ref "U1") (pin "5") (pinfunction "GND1_5") (pintype "input"))
      (node (ref "U2") (pin "12") (pinfunction "GND2_12") (pintype "input"))
      (node (ref "U2") (pin "17") (pinfunction "EP_17") (pintype "input"))
      (node (ref "U2") (pin "5") (pinfunction "GND1_5") (pintype "input"))
      (node (ref "U3") (pin "1") (pinfunction "GND_1") (pintype "power_in"))
      (node (ref "U4") (pin "12") (pinfunction "GND2_12") (pintype "input"))
      (node (ref "U4") (pin "17") (pinfunction "EP_17") (pintype "input"))
      (node (ref "U4") (pin "5") (pinfunction "GND1_5") (pintype "input"))
      (node (ref "U5") (pin "12") (pinfunction "GND2_12") (pintype "input"))
      (node (ref "U5") (pin "17") (pinfunction "EP_17") (pintype "input"))
      (node (ref "U5") (pin "5") (pinfunction "GND1_5") (pintype "input"))
      (node (ref "U6") (pin "1") (pinfunction "GND_1") (pintype "power_in"))
    )
    (net (code "53") (name "unconnected-(U$1-PIN9-PadP$33)") (class "Default")
      (node (ref "U$1") (pin "P$33") (pinfunction "PIN9_P$33") (pintype "bidirectional"))
    )
    (net (code "54") (name "unconnected-(U$1-PIN14-PadP$53)") (class "Default")
      (node (ref "U$1") (pin "P$53") (pinfunction "PIN14_P$53") (pintype "bidirectional"))
    )
    (net (code "55") (name "unconnected-(U$1-PIN15-PadP$57)") (class "Default")
      (node (ref "U$1") (pin "P$57") (pinfunction "PIN15_P$57") (pintype "bidirectional"))
    )
    (net (code "56") (name "unconnected-(U$1-PIN16-PadP$61)") (class "Default")
      (node (ref "U$1") (pin "P$61") (pinfunction "PIN16_P$61") (pintype "bidirectional"))
    )
    (net (code "57") (name "unconnected-(U$1-PIN17-PadP$65)") (class "Default")
      (node (ref "U$1") (pin "P$65") (pinfunction "PIN17_P$65") (pintype "bidirectional"))
    )
    (net (code "58") (name "unconnected-(U$1-PIN18-PadP$69)") (class "Default")
      (node (ref "U$1") (pin "P$69") (pinfunction "PIN18_P$69") (pintype "bidirectional"))
    )
    (net (code "59") (name "unconnected-(U$1-PIN19-PadP$73)") (class "Default")
      (node (ref "U$1") (pin "P$73") (pinfunction "PIN19_P$73") (pintype "bidirectional"))
    )
    (net (code "60") (name "unconnected-(U$1-PIN25-PadP$97)") (class "Default")
      (node (ref "U$1") (pin "P$97") (pinfunction "PIN25_P$97") (pintype "bidirectional"))
    )
    (net (code "61") (name "unconnected-(U$1-PIN26-PadP$101)") (class "Default")
      (node (ref "U$1") (pin "P$101") (pinfunction "PIN26_P$101") (pintype "bidirectional"))
    )
    (net (code "62") (name "unconnected-(U$1-PIN34-PadP$30)") (class "Default")
      (node (ref "U$1") (pin "P$30") (pinfunction "PIN34_P$30") (pintype "bidirectional"))
    )
    (net (code "63") (name "unconnected-(U$1-PIN35-PadP$34)") (class "Default")
      (node (ref "U$1") (pin "P$34") (pinfunction "PIN35_P$34") (pintype "bidirectional"))
    )
    (net (code "64") (name "unconnected-(U$1-PIN37-PadP$42)") (class "Default")
      (node (ref "U$1") (pin "P$42") (pinfunction "PIN37_P$42") (pintype "bidirectional"))
    )
    (net (code "65") (name "unconnected-(U$1-PIN40-PadP$54)") (class "Default")
      (node (ref "U$1") (pin "P$54") (pinfunction "PIN40_P$54") (pintype "bidirectional"))
    )
    (net (code "66") (name "unconnected-(U$1-PIN42-PadP$62)") (class "Default")
      (node (ref "U$1") (pin "P$62") (pinfunction "PIN42_P$62") (pintype "bidirectional"))
    )
    (net (code "67") (name "unconnected-(U$1-PIN44-PadP$70)") (class "Default")
      (node (ref "U$1") (pin "P$70") (pinfunction "PIN44_P$70") (pintype "bidirectional"))
    )
    (net (code "68") (name "unconnected-(U$1-PIN45-PadP$74)") (class "Default")
      (node (ref "U$1") (pin "P$74") (pinfunction "PIN45_P$74") (pintype "bidirectional"))
    )
    (net (code "69") (name "unconnected-(U$1-PIN46-PadP$78)") (class "Default")
      (node (ref "U$1") (pin "P$78") (pinfunction "PIN46_P$78") (pintype "bidirectional"))
    )
    (net (code "70") (name "unconnected-(U$1-PIN51-PadP$98)") (class "Default")
      (node (ref "U$1") (pin "P$98") (pinfunction "PIN51_P$98") (pintype "bidirectional"))
    )
    (net (code "71") (name "unconnected-(U$1-PIN52-PadP$102)") (class "Default")
      (node (ref "U$1") (pin "P$102") (pinfunction "PIN52_P$102") (pintype "bidirectional"))
    )
    (net (code "72") (name "unconnected-(U$1-PIN53-PadP$3)") (class "Default")
      (node (ref "U$1") (pin "P$3") (pinfunction "PIN53_P$3") (pintype "bidirectional"))
    )
    (net (code "73") (name "unconnected-(U$1-PIN54-PadP$7)") (class "Default")
      (node (ref "U$1") (pin "P$7") (pinfunction "PIN54_P$7") (pintype "bidirectional"))
    )
    (net (code "74") (name "unconnected-(U$1-PIN55-PadP$11)") (class "Default")
      (node (ref "U$1") (pin "P$11") (pinfunction "PIN55_P$11") (pintype "bidirectional"))
    )
    (net (code "75") (name "unconnected-(U$1-PIN56-PadP$15)") (class "Default")
      (node (ref "U$1") (pin "P$15") (pinfunction "PIN56_P$15") (pintype "bidirectional"))
    )
    (net (code "76") (name "unconnected-(U$1-PIN57-PadP$19)") (class "Default")
      (node (ref "U$1") (pin "P$19") (pinfunction "PIN57_P$19") (pintype "bidirectional"))
    )
    (net (code "77") (name "unconnected-(U$1-PIN58-PadP$23)") (class "Default")
      (node (ref "U$1") (pin "P$23") (pinfunction "PIN58_P$23") (pintype "bidirectional"))
    )
    (net (code "78") (name "unconnected-(U$1-PIN59-PadP$27)") (class "Default")
      (node (ref "U$1") (pin "P$27") (pinfunction "PIN59_P$27") (pintype "bidirectional"))
    )
    (net (code "79") (name "unconnected-(U$1-PIN60-PadP$31)") (class "Default")
      (node (ref "U$1") (pin "P$31") (pinfunction "PIN60_P$31") (pintype "bidirectional"))
    )
    (net (code "80") (name "unconnected-(U$1-PIN61-PadP$35)") (class "Default")
      (node (ref "U$1") (pin "P$35") (pinfunction "PIN61_P$35") (pintype "bidirectional"))
    )
    (net (code "81") (name "unconnected-(U$1-PIN62-PadP$39)") (class "Default")
      (node (ref "U$1") (pin "P$39") (pinfunction "PIN62_P$39") (pintype "bidirectional"))
    )
    (net (code "82") (name "unconnected-(U$1-PIN63-PadP$43)") (class "Default")
      (node (ref "U$1") (pin "P$43") (pinfunction "PIN63_P$43") (pintype "bidirectional"))
    )
    (net (code "83") (name "unconnected-(U$1-PIN64-PadP$47)") (class "Default")
      (node (ref "U$1") (pin "P$47") (pinfunction "PIN64_P$47") (pintype "bidirectional"))
    )
    (net (code "84") (name "unconnected-(U$1-PIN65-PadP$51)") (class "Default")
      (node (ref "U$1") (pin "P$51") (pinfunction "PIN65_P$51") (pintype "bidirectional"))
    )
    (net (code "85") (name "unconnected-(U$1-PIN66-PadP$55)") (class "Default")
      (node (ref "U$1") (pin "P$55") (pinfunction "PIN66_P$55") (pintype "bidirectional"))
    )
    (net (code "86") (name "unconnected-(U$1-PIN67-PadP$59)") (class "Default")
      (node (ref "U$1") (pin "P$59") (pinfunction "PIN67_P$59") (pintype "bidirectional"))
    )
    (net (code "87") (name "unconnected-(U$1-PIN68-PadP$63)") (class "Default")
      (node (ref "U$1") (pin "P$63") (pinfunction "PIN68_P$63") (pintype "bidirectional"))
    )
    (net (code "88") (name "unconnected-(U$1-PIN69-PadP$67)") (class "Default")
      (node (ref "U$1") (pin "P$67") (pinfunction "PIN69_P$67") (pintype "bidirectional"))
    )
    (net (code "89") (name "unconnected-(U$1-PIN70-PadP$71)") (class "Default")
      (node (ref "U$1") (pin "P$71") (pinfunction "PIN70_P$71") (pintype "bidirectional"))
    )
    (net (code "90") (name "unconnected-(U$1-PIN71-PadP$75)") (class "Default")
      (node (ref "U$1") (pin "P$75") (pinfunction "PIN71_P$75") (pintype "bidirectional"))
    )
    (net (code "91") (name "unconnected-(U$1-PIN72-PadP$79)") (class "Default")
      (node (ref "U$1") (pin "P$79") (pinfunction "PIN72_P$79") (pintype "bidirectional"))
    )
    (net (code "92") (name "unconnected-(U$1-PIN73-PadP$83)") (class "Default")
      (node (ref "U$1") (pin "P$83") (pinfunction "PIN73_P$83") (pintype "bidirectional"))
    )
    (net (code "93") (name "unconnected-(U$1-PIN74-PadP$87)") (class "Default")
      (node (ref "U$1") (pin "P$87") (pinfunction "PIN74_P$87") (pintype "bidirectional"))
    )
    (net (code "94") (name "unconnected-(U$1-PIN75-PadP$91)") (class "Default")
      (node (ref "U$1") (pin "P$91") (pinfunction "PIN75_P$91") (pintype "bidirectional"))
    )
    (net (code "95") (name "unconnected-(U$1-PIN76-PadP$95)") (class "Default")
      (node (ref "U$1") (pin "P$95") (pinfunction "PIN76_P$95") (pintype "bidirectional"))
    )
    (net (code "96") (name "unconnected-(U$1-PIN77-PadP$99)") (class "Default")
      (node (ref "U$1") (pin "P$99") (pinfunction "PIN77_P$99") (pintype "bidirectional"))
    )
    (net (code "97") (name "unconnected-(U$1-PIN78-PadP$103)") (class "Default")
      (node (ref "U$1") (pin "P$103") (pinfunction "PIN78_P$103") (pintype "bidirectional"))
    )
    (net (code "98") (name "unconnected-(U$1-PIN79-PadP$4)") (class "Default")
      (node (ref "U$1") (pin "P$4") (pinfunction "PIN79_P$4") (pintype "bidirectional"))
    )
    (net (code "99") (name "unconnected-(U$1-PIN80-PadP$8)") (class "Default")
      (node (ref "U$1") (pin "P$8") (pinfunction "PIN80_P$8") (pintype "bidirectional"))
    )
    (net (code "100") (name "unconnected-(U$1-PIN81-PadP$12)") (class "Default")
      (node (ref "U$1") (pin "P$12") (pinfunction "PIN81_P$12") (pintype "bidirectional"))
    )
    (net (code "101") (name "unconnected-(U$1-PIN82-PadP$16)") (class "Default")
      (node (ref "U$1") (pin "P$16") (pinfunction "PIN82_P$16") (pintype "bidirectional"))
    )
    (net (code "102") (name "unconnected-(U$1-PIN83-PadP$20)") (class "Default")
      (node (ref "U$1") (pin "P$20") (pinfunction "PIN83_P$20") (pintype "bidirectional"))
    )
    (net (code "103") (name "unconnected-(U$1-PIN84-PadP$24)") (class "Default")
      (node (ref "U$1") (pin "P$24") (pinfunction "PIN84_P$24") (pintype "bidirectional"))
    )
    (net (code "104") (name "unconnected-(U$1-PIN85-PadP$28)") (class "Default")
      (node (ref "U$1") (pin "P$28") (pinfunction "PIN85_P$28") (pintype "bidirectional"))
    )
    (net (code "105") (name "unconnected-(U$1-PIN86-PadP$32)") (class "Default")
      (node (ref "U$1") (pin "P$32") (pinfunction "PIN86_P$32") (pintype "bidirectional"))
    )
    (net (code "106") (name "unconnected-(U$1-PIN87-PadP$36)") (class "Default")
      (node (ref "U$1") (pin "P$36") (pinfunction "PIN87_P$36") (pintype "bidirectional"))
    )
    (net (code "107") (name "unconnected-(U$1-PIN88-PadP$40)") (class "Default")
      (node (ref "U$1") (pin "P$40") (pinfunction "PIN88_P$40") (pintype "bidirectional"))
    )
    (net (code "108") (name "unconnected-(U$1-PIN89-PadP$44)") (class "Default")
      (node (ref "U$1") (pin "P$44") (pinfunction "PIN89_P$44") (pintype "bidirectional"))
    )
    (net (code "109") (name "unconnected-(U$1-PIN90-PadP$48)") (class "Default")
      (node (ref "U$1") (pin "P$48") (pinfunction "PIN90_P$48") (pintype "bidirectional"))
    )
    (net (code "110") (name "unconnected-(U$1-PIN91-PadP$52)") (class "Default")
      (node (ref "U$1") (pin "P$52") (pinfunction "PIN91_P$52") (pintype "bidirectional"))
    )
    (net (code "111") (name "unconnected-(U$1-PIN92-PadP$56)") (class "Default")
      (node (ref "U$1") (pin "P$56") (pinfunction "PIN92_P$56") (pintype "bidirectional"))
    )
    (net (code "112") (name "unconnected-(U$1-PIN93-PadP$60)") (class "Default")
      (node (ref "U$1") (pin "P$60") (pinfunction "PIN93_P$60") (pintype "bidirectional"))
    )
    (net (code "113") (name "unconnected-(U$1-PIN94-PadP$64)") (class "Default")
      (node (ref "U$1") (pin "P$64") (pinfunction "PIN94_P$64") (pintype "bidirectional"))
    )
    (net (code "114") (name "unconnected-(U$1-PIN95-PadP$68)") (class "Default")
      (node (ref "U$1") (pin "P$68") (pinfunction "PIN95_P$68") (pintype "bidirectional"))
    )
    (net (code "115") (name "unconnected-(U$1-PIN96-PadP$72)") (class "Default")
      (node (ref "U$1") (pin "P$72") (pinfunction "PIN96_P$72") (pintype "bidirectional"))
    )
    (net (code "116") (name "unconnected-(U$1-PIN97-PadP$76)") (class "Default")
      (node (ref "U$1") (pin "P$76") (pinfunction "PIN97_P$76") (pintype "bidirectional"))
    )
    (net (code "117") (name "unconnected-(U$1-PIN98-PadP$80)") (class "Default")
      (node (ref "U$1") (pin "P$80") (pinfunction "PIN98_P$80") (pintype "bidirectional"))
    )
    (net (code "118") (name "unconnected-(U$1-PIN99-PadP$84)") (class "Default")
      (node (ref "U$1") (pin "P$84") (pinfunction "PIN99_P$84") (pintype "bidirectional"))
    )
    (net (code "119") (name "unconnected-(U$1-PIN100-PadP$88)") (class "Default")
      (node (ref "U$1") (pin "P$88") (pinfunction "PIN100_P$88") (pintype "bidirectional"))
    )
    (net (code "120") (name "unconnected-(U$1-PIN101-PadP$92)") (class "Default")
      (node (ref "U$1") (pin "P$92") (pinfunction "PIN101_P$92") (pintype "bidirectional"))
    )
    (net (code "121") (name "unconnected-(U$1-PIN102-PadP$96)") (class "Default")
      (node (ref "U$1") (pin "P$96") (pinfunction "PIN102_P$96") (pintype "bidirectional"))
    )
    (net (code "122") (name "unconnected-(U$1-PIN103-PadP$100)") (class "Default")
      (node (ref "U$1") (pin "P$100") (pinfunction "PIN103_P$100") (pintype "bidirectional"))
    )
    (net (code "123") (name "unconnected-(U$1-PIN104-PadP$104)") (class "Default")
      (node (ref "U$1") (pin "P$104") (pinfunction "PIN104_P$104") (pintype "bidirectional"))
    )
  )
)
